# carrier_card_s2.net
KiCad netlist of a schematic drawn in Altium Designer
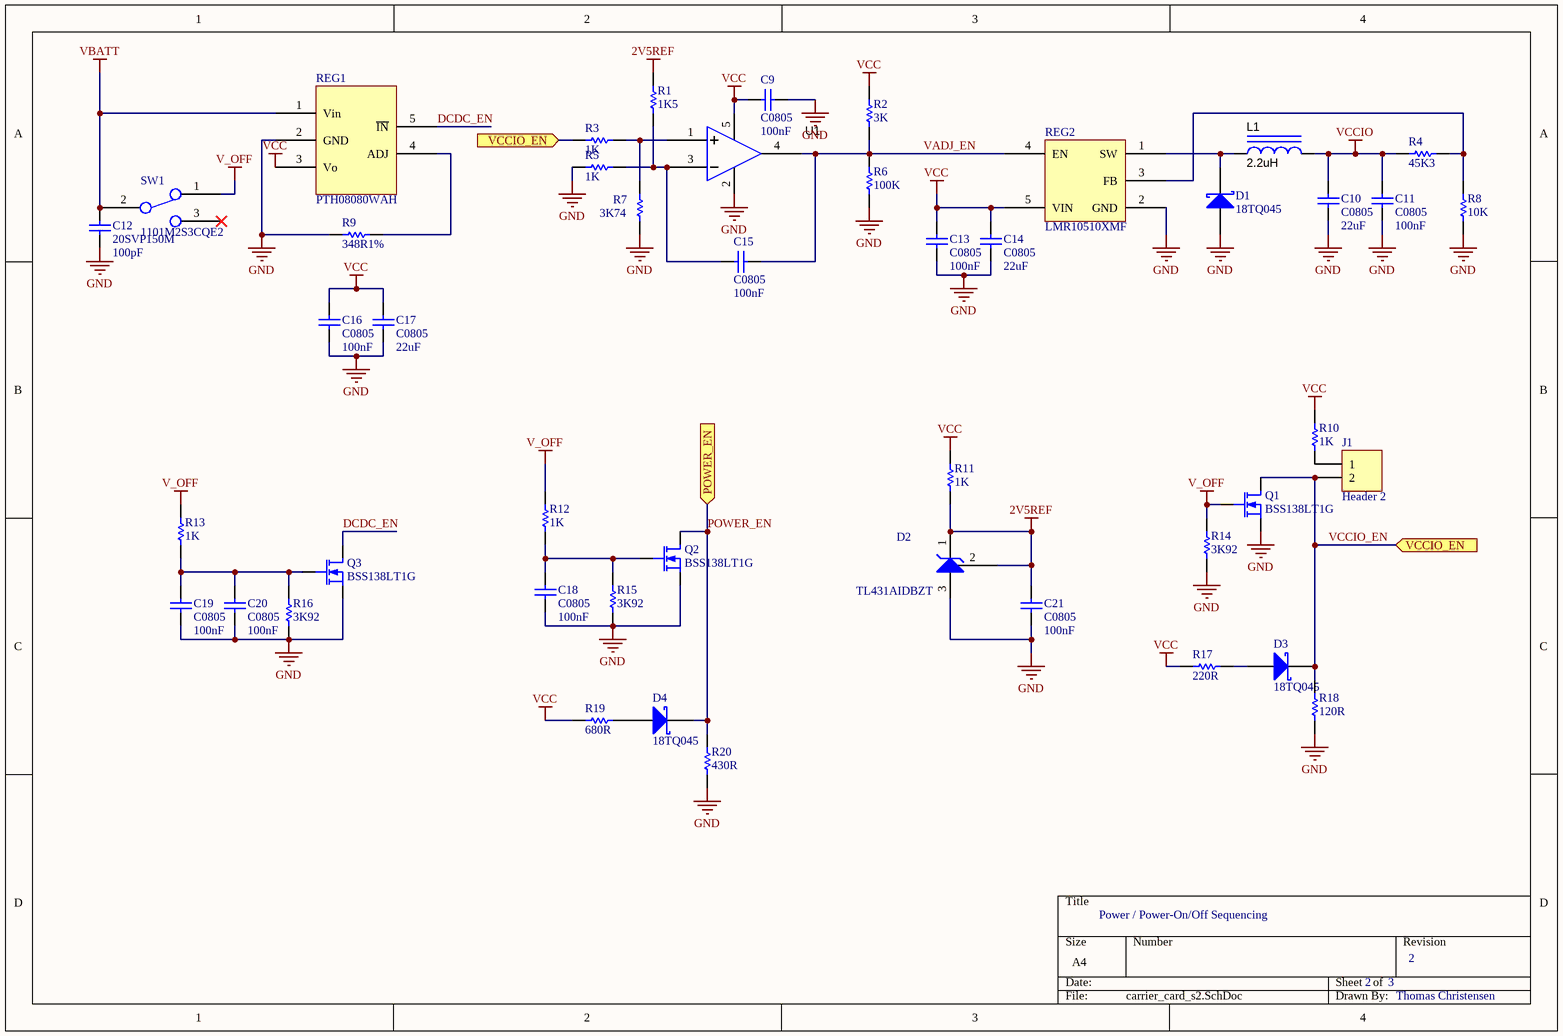
[diagram p0: carrier_card_s2.SchDoc]

(export (version "E")
  (design (tool "Eeschema 10.0.6"))
  (components
    (comp (ref "C9")
      (value "C0805")
      (footprint "0805")
      (description "Ceramic Chip Capacitor - Standard")
      (fields (field (name "ALTIUM_VALUE") "100nF") (field (name "PUBLISHER") "Altium Limited"))
      (libsource (lib "KEMET Chip Capacitor") (part "C0805"))
    )
    (comp (ref "C10")
      (value "C0805")
      (footprint "0805")
      (description "Ceramic Chip Capacitor - Standard")
      (fields (field (name "ALTIUM_VALUE") "22uF") (field (name "PUBLISHER") "Altium Limited"))
      (libsource (lib "KEMET Chip Capacitor") (part "C0805"))
    )
    (comp (ref "C11")
      (value "C0805")
      (footprint "0805")
      (description "Ceramic Chip Capacitor - Standard")
      (fields (field (name "ALTIUM_VALUE") "100nF") (field (name "PUBLISHER") "Altium Limited"))
      (libsource (lib "KEMET Chip Capacitor") (part "C0805"))
    )
    (comp (ref "C12")
      (value "20SVP150M")
      (footprint "20SVP150M_FP")
      (description "Capacitor (Semiconductor SIM Model)")
      (fields (field (name "ALTIUM_VALUE") "100pF") (field (name "PUBLISHER") "Altium Limited"))
      (libsource (lib "swarmbot_schematic_library") (part "20SVP150M"))
    )
    (comp (ref "C13")
      (value "C0805")
      (footprint "0805")
      (description "Ceramic Chip Capacitor - Standard")
      (fields (field (name "ALTIUM_VALUE") "100nF") (field (name "PUBLISHER") "Altium Limited"))
      (libsource (lib "KEMET Chip Capacitor") (part "C0805"))
    )
    (comp (ref "C14")
      (value "C0805")
      (footprint "0805")
      (description "Ceramic Chip Capacitor - Standard")
      (fields (field (name "ALTIUM_VALUE") "22uF") (field (name "PUBLISHER") "Altium Limited"))
      (libsource (lib "KEMET Chip Capacitor") (part "C0805"))
    )
    (comp (ref "C15")
      (value "C0805")
      (footprint "0805")
      (description "Ceramic Chip Capacitor - Standard")
      (fields (field (name "ALTIUM_VALUE") "100nF") (field (name "PUBLISHER") "Altium Limited"))
      (libsource (lib "KEMET Chip Capacitor") (part "C0805"))
    )
    (comp (ref "C16")
      (value "C0805")
      (footprint "0805")
      (description "Ceramic Chip Capacitor - Standard")
      (fields (field (name "ALTIUM_VALUE") "100nF") (field (name "PUBLISHER") "Altium Limited"))
      (libsource (lib "KEMET Chip Capacitor") (part "C0805"))
    )
    (comp (ref "C17")
      (value "C0805")
      (footprint "0805")
      (description "Ceramic Chip Capacitor - Standard")
      (fields (field (name "ALTIUM_VALUE") "22uF") (field (name "PUBLISHER") "Altium Limited"))
      (libsource (lib "KEMET Chip Capacitor") (part "C0805"))
    )
    (comp (ref "C18")
      (value "C0805")
      (footprint "0805")
      (description "Ceramic Chip Capacitor - Standard")
      (fields (field (name "ALTIUM_VALUE") "100nF") (field (name "PUBLISHER") "Altium Limited"))
      (libsource (lib "KEMET Chip Capacitor") (part "C0805"))
    )
    (comp (ref "C19")
      (value "C0805")
      (footprint "0805")
      (description "Ceramic Chip Capacitor - Standard")
      (fields (field (name "ALTIUM_VALUE") "100nF") (field (name "PUBLISHER") "Altium Limited"))
      (libsource (lib "KEMET Chip Capacitor") (part "C0805"))
    )
    (comp (ref "C20")
      (value "C0805")
      (footprint "0805")
      (description "Ceramic Chip Capacitor - Standard")
      (fields (field (name "ALTIUM_VALUE") "100nF") (field (name "PUBLISHER") "Altium Limited"))
      (libsource (lib "KEMET Chip Capacitor") (part "C0805"))
    )
    (comp (ref "C21")
      (value "C0805")
      (footprint "0805")
      (description "Ceramic Chip Capacitor - Standard")
      (fields (field (name "ALTIUM_VALUE") "100nF") (field (name "PUBLISHER") "Altium Limited"))
      (libsource (lib "KEMET Chip Capacitor") (part "C0805"))
    )
    (comp (ref "D1")
      (value "18TQ045")
      (footprint "POWERDI-123")
      (description "Schottky Rectifier")
      (fields (field (name "PUBLISHER") "Altium Limited"))
      (libsource (lib "swarmbot_schematic_library") (part "18TQ045"))
    )
    (comp (ref "D2")
      (value "TL431AIDBZT")
      (footprint "SOT-23_N")
      (description "Variable voltage  reference")
      (fields (field (name "PUBLISHER") "Altium Limited"))
      (libsource (lib "swarmbot_schematic_library") (part "TL431AIDBZT"))
    )
    (comp (ref "D3")
      (value "18TQ045")
      (footprint "POWERDI-123")
      (description "Schottky Rectifier")
      (fields (field (name "PUBLISHER") "Altium Limited"))
      (libsource (lib "swarmbot_schematic_library") (part "18TQ045"))
    )
    (comp (ref "D4")
      (value "18TQ045")
      (footprint "POWERDI-123")
      (description "Schottky Rectifier")
      (fields (field (name "PUBLISHER") "Altium Limited"))
      (libsource (lib "swarmbot_schematic_library") (part "18TQ045"))
    )
    (comp (ref "J1")
      (value "Header 2")
      (footprint "HDR1X2")
      (description "Header, 2-Pin")
      (fields (field (name "PUBLISHER") "Altium Limited"))
      (libsource (lib "Miscellaneous Connectors") (part "Header 2"))
    )
    (comp (ref "L1")
      (value "2.2uH")
      (footprint "SRN5020-2R2Y_FP")
      (description "SRN5020-2R2Y")
      (fields (field (name "TOLERANCE") "±20%"))
      (libsource (lib "swarmbot_schematic_library") (part "SRN5020-2R2Y"))
    )
    (comp (ref "Q1")
      (value "BSS138LT1G")
      (footprint "SOT-23B")
      (description "N-Channel MOSFET")
      (fields (field (name "PUBLISHER") "Altium Limited"))
      (libsource (lib "swarmbot_schematic_library") (part "BSS138LT1G"))
    )
    (comp (ref "Q2")
      (value "BSS138LT1G")
      (footprint "SOT-23B")
      (description "N-Channel MOSFET")
      (fields (field (name "PUBLISHER") "Altium Limited"))
      (libsource (lib "swarmbot_schematic_library") (part "BSS138LT1G"))
    )
    (comp (ref "Q3")
      (value "BSS138LT1G")
      (footprint "SOT-23B")
      (description "N-Channel MOSFET")
      (fields (field (name "PUBLISHER") "Altium Limited"))
      (libsource (lib "swarmbot_schematic_library") (part "BSS138LT1G"))
    )
    (comp (ref "R1")
      (value "1K5")
      (footprint "ERA-0603")
      (fields (field (name "PUBLISHER") "Altium Limited"))
      (libsource (lib "Panasonic Resistor") (part "ERA3Y"))
    )
    (comp (ref "R2")
      (value "3K")
      (footprint "ERA-0603")
      (fields (field (name "PUBLISHER") "Altium Limited"))
      (libsource (lib "Panasonic Resistor") (part "ERA3Y"))
    )
    (comp (ref "R3")
      (value "1K")
      (footprint "ERA-0603")
      (fields (field (name "PUBLISHER") "Altium Limited"))
      (libsource (lib "Panasonic Resistor") (part "ERA3Y"))
    )
    (comp (ref "R4")
      (value "45K3")
      (footprint "ERA-0603")
      (fields (field (name "PUBLISHER") "Altium Limited"))
      (libsource (lib "Panasonic Resistor") (part "ERA3Y"))
    )
    (comp (ref "R5")
      (value "1K")
      (footprint "ERA-0603")
      (fields (field (name "PUBLISHER") "Altium Limited"))
      (libsource (lib "Panasonic Resistor") (part "ERA3Y"))
    )
    (comp (ref "R6")
      (value "100K")
      (footprint "ERA-0603")
      (fields (field (name "PUBLISHER") "Altium Limited"))
      (libsource (lib "Panasonic Resistor") (part "ERA3Y"))
    )
    (comp (ref "R7")
      (value "3K74")
      (footprint "ERA-0603")
      (fields (field (name "PUBLISHER") "Altium Limited"))
      (libsource (lib "Panasonic Resistor") (part "ERA3Y"))
    )
    (comp (ref "R8")
      (value "10K")
      (footprint "ERA-0603")
      (fields (field (name "PUBLISHER") "Altium Limited"))
      (libsource (lib "Panasonic Resistor") (part "ERA3Y"))
    )
    (comp (ref "R9")
      (value "348R1%")
      (footprint "ERA-0805")
      (fields (field (name "PUBLISHER") "Altium Limited"))
      (libsource (lib "Panasonic Resistor") (part "ERA6Y"))
    )
    (comp (ref "R10")
      (value "1K")
      (footprint "ERA-0603")
      (fields (field (name "PUBLISHER") "Altium Limited"))
      (libsource (lib "Panasonic Resistor") (part "ERA3Y"))
    )
    (comp (ref "R11")
      (value "1K")
      (footprint "ERA-0603")
      (fields (field (name "PUBLISHER") "Altium Limited"))
      (libsource (lib "Panasonic Resistor") (part "ERA3Y"))
    )
    (comp (ref "R12")
      (value "1K")
      (footprint "ERA-0603")
      (fields (field (name "PUBLISHER") "Altium Limited"))
      (libsource (lib "Panasonic Resistor") (part "ERA3Y"))
    )
    (comp (ref "R13")
      (value "1K")
      (footprint "ERA-0603")
      (fields (field (name "PUBLISHER") "Altium Limited"))
      (libsource (lib "Panasonic Resistor") (part "ERA3Y"))
    )
    (comp (ref "R14")
      (value "3K92")
      (footprint "ERA-0603")
      (fields (field (name "PUBLISHER") "Altium Limited"))
      (libsource (lib "Panasonic Resistor") (part "ERA3Y"))
    )
    (comp (ref "R15")
      (value "3K92")
      (footprint "ERA-0603")
      (fields (field (name "PUBLISHER") "Altium Limited"))
      (libsource (lib "Panasonic Resistor") (part "ERA3Y"))
    )
    (comp (ref "R16")
      (value "3K92")
      (footprint "ERA-0603")
      (fields (field (name "PUBLISHER") "Altium Limited"))
      (libsource (lib "Panasonic Resistor") (part "ERA3Y"))
    )
    (comp (ref "R17")
      (value "220R")
      (footprint "ERA-0603")
      (fields (field (name "PUBLISHER") "Altium Limited"))
      (libsource (lib "Panasonic Resistor") (part "ERA3Y"))
    )
    (comp (ref "R18")
      (value "120R")
      (footprint "ERA-0603")
      (fields (field (name "PUBLISHER") "Altium Limited"))
      (libsource (lib "Panasonic Resistor") (part "ERA3Y"))
    )
    (comp (ref "R19")
      (value "680R")
      (footprint "ERA-0603")
      (fields (field (name "PUBLISHER") "Altium Limited"))
      (libsource (lib "Panasonic Resistor") (part "ERA3Y"))
    )
    (comp (ref "R20")
      (value "430R")
      (footprint "ERA-0603")
      (fields (field (name "PUBLISHER") "Altium Limited"))
      (libsource (lib "Panasonic Resistor") (part "ERA3Y"))
    )
    (comp (ref "REG1")
      (value "PTH08080WAH")
      (footprint "PTH08080W_FP")
      (libsource (lib "swarmbot_schematic_library") (part "PTH08080WAH"))
    )
    (comp (ref "REG2")
      (value "LMR10510XMF")
      (footprint "SOT23-5")
      (libsource (lib "swarmbot_schematic_library") (part "LMR10510XMF"))
    )
    (comp (ref "SW1")
      (value "1101M2S3CQE2")
      (footprint "1101M2S3CQE2_FP")
      (libsource (lib "swarmbot_schematic_library") (part "1101M2S3CQE2"))
    )
    (comp (ref "U1")
      (value "TLV2702")
      (footprint "SOT23-5")
      (description "IC SMD AMP+COMPAR Combo SOIC-8")
      (libsource (lib "swarmbot_schematic_library") (part "LMV331QDBVRQ1"))
    )
  )
  (nets
    (net (code "1") (name "/DCDC_EN") (class "Default")
      (node (ref "Q3") (pin "3") (pinfunction "D_3") (pintype "passive"))
      (node (ref "REG1") (pin "5") (pinfunction "~{IN}_5") (pintype "passive"))
    )
    (net (code "2") (name "/POWER_EN") (class "Default")
      (node (ref "D4") (pin "2") (pinfunction "K_2") (pintype "passive"))
      (node (ref "Q2") (pin "3") (pinfunction "D_3") (pintype "passive"))
      (node (ref "R20") (pin "2") (pinfunction "2_2") (pintype "passive"))
    )
    (net (code "3") (name "/VADJ_EN") (class "Default")
      (node (ref "C15") (pin "2") (pinfunction "2_2") (pintype "passive"))
      (node (ref "R2") (pin "1") (pinfunction "1_1") (pintype "passive"))
      (node (ref "R6") (pin "2") (pinfunction "2_2") (pintype "passive"))
      (node (ref "REG2") (pin "4") (pinfunction "EN_4") (pintype "passive"))
      (node (ref "U1") (pin "4") (pinfunction "OUT_4") (pintype "passive"))
    )
    (net (code "4") (name "/VCCIO_EN") (class "Default")
      (node (ref "D3") (pin "2") (pinfunction "K_2") (pintype "passive"))
      (node (ref "J1") (pin "2") (pinfunction "2_2") (pintype "passive"))
      (node (ref "Q1") (pin "3") (pinfunction "D_3") (pintype "passive"))
      (node (ref "R18") (pin "2") (pinfunction "2_2") (pintype "passive"))
      (node (ref "R3") (pin "1") (pinfunction "1_1") (pintype "passive"))
    )
    (net (code "5") (name "2V5REF") (class "Default")
      (node (ref "C21") (pin "2") (pinfunction "2_2") (pintype "passive"))
      (node (ref "D2") (pin "1") (pinfunction "K_1") (pintype "passive"))
      (node (ref "D2") (pin "2") (pinfunction "4_2") (pintype "passive"))
      (node (ref "R1") (pin "2") (pinfunction "2_2") (pintype "passive"))
      (node (ref "R11") (pin "1") (pinfunction "1_1") (pintype "passive"))
    )
    (net (code "6") (name "GND") (class "Default")
      (node (ref "C10") (pin "1") (pinfunction "1_1") (pintype "passive"))
      (node (ref "C11") (pin "1") (pinfunction "1_1") (pintype "passive"))
      (node (ref "C12") (pin "1") (pinfunction "1_1") (pintype "passive"))
      (node (ref "C13") (pin "1") (pinfunction "1_1") (pintype "passive"))
      (node (ref "C14") (pin "1") (pinfunction "1_1") (pintype "passive"))
      (node (ref "C16") (pin "1") (pinfunction "1_1") (pintype "passive"))
      (node (ref "C17") (pin "1") (pinfunction "1_1") (pintype "passive"))
      (node (ref "C18") (pin "1") (pinfunction "1_1") (pintype "passive"))
      (node (ref "C19") (pin "1") (pinfunction "1_1") (pintype "passive"))
      (node (ref "C20") (pin "1") (pinfunction "1_1") (pintype "passive"))
      (node (ref "C21") (pin "1") (pinfunction "1_1") (pintype "passive"))
      (node (ref "C9") (pin "2") (pinfunction "2_2") (pintype "passive"))
      (node (ref "D1") (pin "1") (pinfunction "A_1") (pintype "passive"))
      (node (ref "D2") (pin "3") (pinfunction "A_3") (pintype "passive"))
      (node (ref "Q1") (pin "2") (pinfunction "S_2") (pintype "passive"))
      (node (ref "Q2") (pin "2") (pinfunction "S_2") (pintype "passive"))
      (node (ref "Q3") (pin "2") (pinfunction "S_2") (pintype "passive"))
      (node (ref "R14") (pin "1") (pinfunction "1_1") (pintype "passive"))
      (node (ref "R15") (pin "1") (pinfunction "1_1") (pintype "passive"))
      (node (ref "R16") (pin "1") (pinfunction "1_1") (pintype "passive"))
      (node (ref "R18") (pin "1") (pinfunction "1_1") (pintype "passive"))
      (node (ref "R20") (pin "1") (pinfunction "1_1") (pintype "passive"))
      (node (ref "R5") (pin "1") (pinfunction "1_1") (pintype "passive"))
      (node (ref "R6") (pin "1") (pinfunction "1_1") (pintype "passive"))
      (node (ref "R7") (pin "1") (pinfunction "1_1") (pintype "passive"))
      (node (ref "R8") (pin "1") (pinfunction "1_1") (pintype "passive"))
      (node (ref "R9") (pin "1") (pinfunction "1_1") (pintype "passive"))
      (node (ref "REG1") (pin "2") (pinfunction "GND_2") (pintype "passive"))
      (node (ref "REG2") (pin "2") (pinfunction "GND_2") (pintype "passive"))
      (node (ref "U1") (pin "2") (pinfunction "GND_2") (pintype "power_in"))
    )
    (net (code "7") (name "Net-(D1-K)") (class "Default")
      (node (ref "D1") (pin "2") (pinfunction "K_2") (pintype "passive"))
      (node (ref "L1") (pin "1") (pinfunction "1_1") (pintype "passive"))
      (node (ref "REG2") (pin "1") (pinfunction "SW_1") (pintype "passive"))
    )
    (net (code "8") (name "Net-(D3-A)") (class "Default")
      (node (ref "D3") (pin "1") (pinfunction "A_1") (pintype "passive"))
      (node (ref "R17") (pin "2") (pinfunction "2_2") (pintype "passive"))
    )
    (net (code "9") (name "Net-(D4-A)") (class "Default")
      (node (ref "D4") (pin "1") (pinfunction "A_1") (pintype "passive"))
      (node (ref "R19") (pin "2") (pinfunction "2_2") (pintype "passive"))
    )
    (net (code "10") (name "Net-(J1-Pad1)") (class "Default")
      (node (ref "J1") (pin "1") (pinfunction "1_1") (pintype "passive"))
      (node (ref "R10") (pin "1") (pinfunction "1_1") (pintype "passive"))
    )
    (net (code "11") (name "Net-(Q2-G)") (class "Default")
      (node (ref "C18") (pin "2") (pinfunction "2_2") (pintype "passive"))
      (node (ref "Q2") (pin "1") (pinfunction "G_1") (pintype "passive"))
      (node (ref "R12") (pin "1") (pinfunction "1_1") (pintype "passive"))
      (node (ref "R15") (pin "2") (pinfunction "2_2") (pintype "passive"))
    )
    (net (code "12") (name "Net-(Q3-G)") (class "Default")
      (node (ref "C19") (pin "2") (pinfunction "2_2") (pintype "passive"))
      (node (ref "C20") (pin "2") (pinfunction "2_2") (pintype "passive"))
      (node (ref "Q3") (pin "1") (pinfunction "G_1") (pintype "passive"))
      (node (ref "R13") (pin "1") (pinfunction "1_1") (pintype "passive"))
      (node (ref "R16") (pin "2") (pinfunction "2_2") (pintype "passive"))
    )
    (net (code "13") (name "Net-(REG1-ADJ)") (class "Default")
      (node (ref "R9") (pin "2") (pinfunction "2_2") (pintype "passive"))
      (node (ref "REG1") (pin "4") (pinfunction "ADJ_4") (pintype "passive"))
    )
    (net (code "14") (name "Net-(REG2-FB)") (class "Default")
      (node (ref "R4") (pin "2") (pinfunction "2_2") (pintype "passive"))
      (node (ref "R8") (pin "2") (pinfunction "2_2") (pintype "passive"))
      (node (ref "REG2") (pin "3") (pinfunction "FB_3") (pintype "passive"))
    )
    (net (code "15") (name "Net-(U1-IN+)") (class "Default")
      (node (ref "R3") (pin "2") (pinfunction "2_2") (pintype "passive"))
      (node (ref "R7") (pin "2") (pinfunction "2_2") (pintype "passive"))
      (node (ref "U1") (pin "1") (pinfunction "IN+_1") (pintype "passive"))
    )
    (net (code "16") (name "Net-(U1-IN-)") (class "Default")
      (node (ref "C15") (pin "1") (pinfunction "1_1") (pintype "passive"))
      (node (ref "R1") (pin "1") (pinfunction "1_1") (pintype "passive"))
      (node (ref "R5") (pin "2") (pinfunction "2_2") (pintype "passive"))
      (node (ref "U1") (pin "3") (pinfunction "IN-_3") (pintype "passive"))
    )
    (net (code "17") (name "VBATT") (class "Default")
      (node (ref "C12") (pin "2") (pinfunction "2_2") (pintype "passive"))
      (node (ref "REG1") (pin "1") (pinfunction "Vin_1") (pintype "passive"))
      (node (ref "SW1") (pin "2") (pinfunction "2_2") (pintype "passive"))
    )
    (net (code "18") (name "VCC") (class "Default")
      (node (ref "C13") (pin "2") (pinfunction "2_2") (pintype "passive"))
      (node (ref "C14") (pin "2") (pinfunction "2_2") (pintype "passive"))
      (node (ref "C16") (pin "2") (pinfunction "2_2") (pintype "passive"))
      (node (ref "C17") (pin "2") (pinfunction "2_2") (pintype "passive"))
      (node (ref "C9") (pin "1") (pinfunction "1_1") (pintype "passive"))
      (node (ref "R10") (pin "2") (pinfunction "2_2") (pintype "passive"))
      (node (ref "R11") (pin "2") (pinfunction "2_2") (pintype "passive"))
      (node (ref "R17") (pin "1") (pinfunction "1_1") (pintype "passive"))
      (node (ref "R19") (pin "1") (pinfunction "1_1") (pintype "passive"))
      (node (ref "R2") (pin "2") (pinfunction "2_2") (pintype "passive"))
      (node (ref "REG1") (pin "3") (pinfunction "Vo_3") (pintype "passive"))
      (node (ref "REG2") (pin "5") (pinfunction "VIN_5") (pintype "passive"))
      (node (ref "U1") (pin "5") (pinfunction "Vcc_5") (pintype "power_in"))
    )
    (net (code "19") (name "VCCIO") (class "Default")
      (node (ref "C10") (pin "2") (pinfunction "2_2") (pintype "passive"))
      (node (ref "C11") (pin "2") (pinfunction "2_2") (pintype "passive"))
      (node (ref "L1") (pin "2") (pinfunction "2_2") (pintype "passive"))
      (node (ref "R4") (pin "1") (pinfunction "1_1") (pintype "passive"))
    )
    (net (code "20") (name "V_OFF") (class "Default")
      (node (ref "Q1") (pin "1") (pinfunction "G_1") (pintype "passive"))
      (node (ref "R12") (pin "2") (pinfunction "2_2") (pintype "passive"))
      (node (ref "R13") (pin "2") (pinfunction "2_2") (pintype "passive"))
      (node (ref "R14") (pin "2") (pinfunction "2_2") (pintype "passive"))
      (node (ref "SW1") (pin "1") (pinfunction "1_1") (pintype "passive"))
    )
    (net (code "21") (name "unconnected-(SW1-Pad3)") (class "Default")
      (node (ref "SW1") (pin "3") (pinfunction "3_3") (pintype "passive+no_connect"))
    )
  )
)
